# Carte_Alim_2020_TOP.net
KiCad netlist of a schematic drawn in Altium Designer
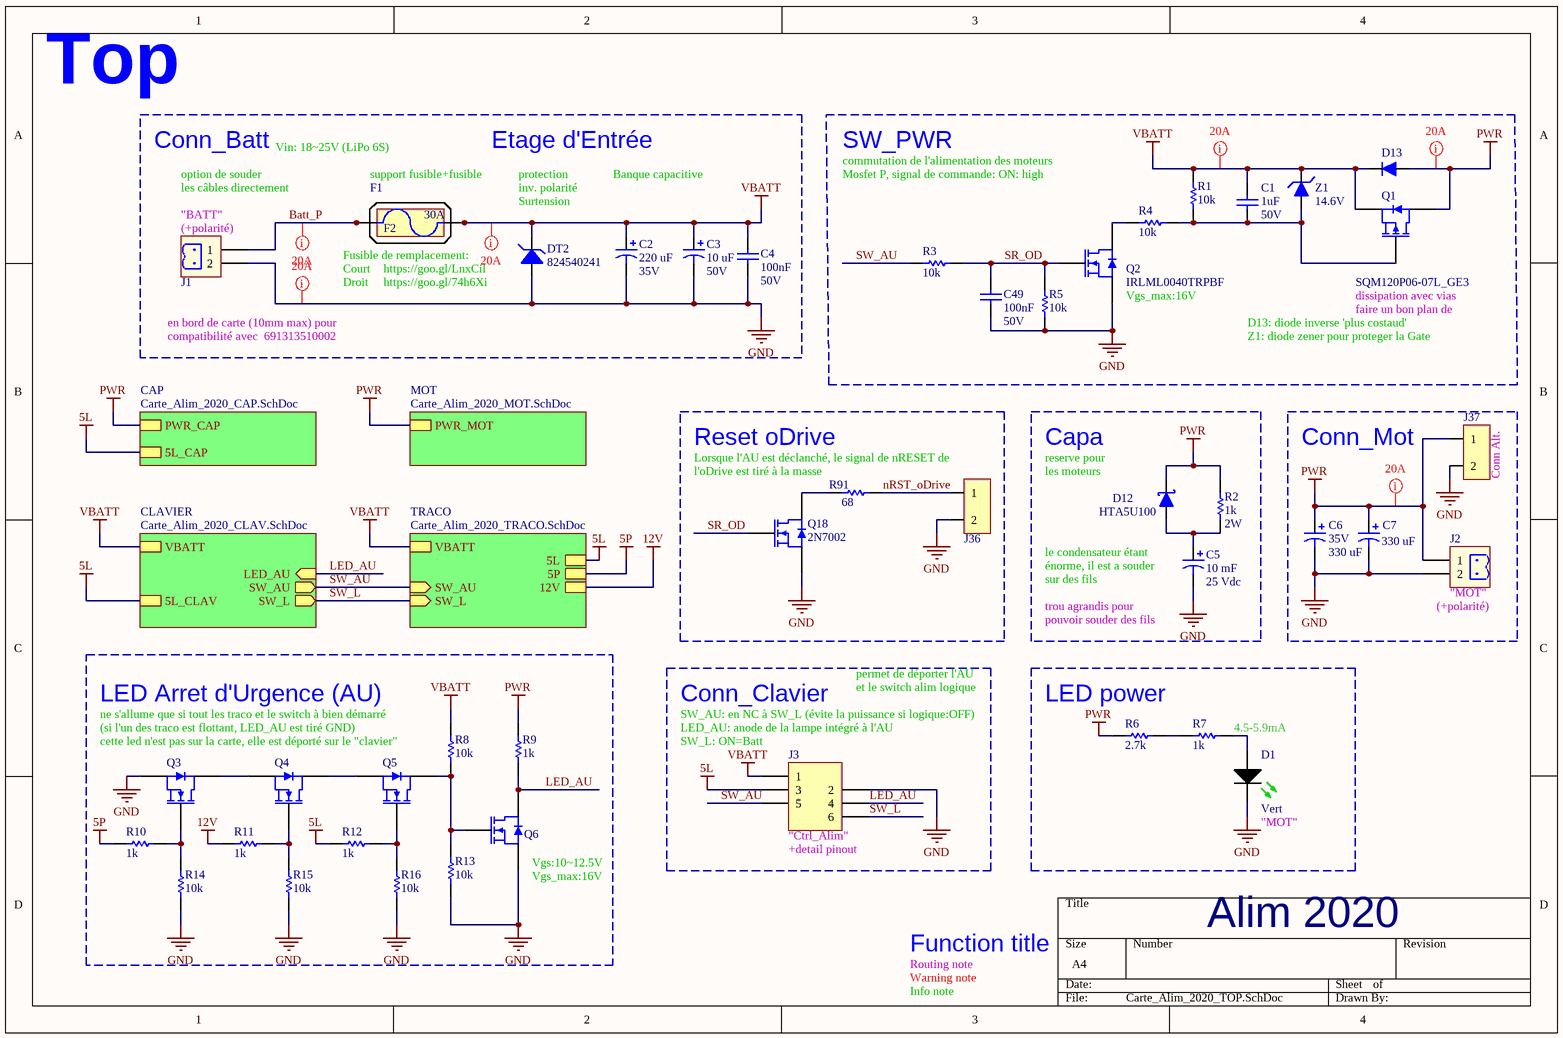
[diagram p0: Carte_Alim_2020_TOP.SchDoc]

(export (version "E")
  (design (tool "Eeschema 10.0.6"))
  (components
    (comp (ref "C1")
      (value "1uF")
      (footprint "WCAP-CSGP_0805, 2x1.25x1.25")
      (description "CAP CER 1uF 50V X7R 0805")
      (fields
        (field (name "MANUFACTURER") "Wurth Elektronik")
        (field (name "MANUFACTURER PART NUMBER") "885012207103")
        (field (name "RATEDVOLTAGE") "50V")
      )
      (libsource (lib "Condensateur") (part "WCAP-CSGP, 885012207103"))
    )
    (comp (ref "C2")
      (value "220 uF")
      (footprint "WCAP-ATG8_8x11.5x3.5x0.5")
      (description "CAP Alu 220 UF 20% 35 V")
      (fields
        (field (name "MANUFACTURER") "Wurth Elektronik")
        (field (name "MANUFACTURER PART NUMBER") "860010574011")
        (field (name "RATEDVOLTAGE") "35V")
      )
      (libsource (lib "Condensateur") (part "WCAP-ATG8, 860010574011"))
    )
    (comp (ref "C3")
      (value "10 uF")
      (footprint "WCAP-ATG8_5x11x2x0.5")
      (description "CAP Alu 10 UF 20% 50 V")
      (fields
        (field (name "RATEDVOLTAGE") "50V")
        (field (name "MANUFACTURER") "Wurth Elektronik")
        (field (name "MANUFACTURER PART NUMBER") "860010672009")
      )
      (libsource (lib "Condensateur") (part "WCAP-ATG8, 860010672009"))
    )
    (comp (ref "C4")
      (value "100nF")
      (footprint "WCAP-CSGP_0603, 1.6x0.8x0.8")
      (description "CAP CER 100nF 50V X7R 0603")
      (fields
        (field (name "RATEDVOLTAGE") "50V")
        (field (name "MANUFACTURER") "Wurth Elektronik")
        (field (name "MANUFACTURER PART NUMBER") "885012206095")
      )
      (libsource (lib "Condensateur") (part "WCAP-CSGP, 885012206095"))
    )
    (comp (ref "C5")
      (value "10 mF")
      (footprint "WCAP-ATG8_22x41x10x0.8")
      (description "CAP Alu 10'000 UF 25 V")
      (fields
        (field (name "MANUFACTURER PART NUMBER") "860010483029")
        (field (name "MANUFACTURER") "Wurth Elektronik")
        (field (name "RATED VOLTAGE") "25 Vdc")
      )
      (libsource (lib "Condensateur") (part "WCAP-ATG8, 860010483029"))
    )
    (comp (ref "C6")
      (value "330 uF")
      (footprint "WCAP-ATG8_10x12.5x5x0.6")
      (description "CAP Alu 330 UF 20% 35 V")
      (fields
        (field (name "MANUFACTURER") "Wurth Elektronik")
        (field (name "MANUFACTURER PART NUMBER") "860010575012")
        (field (name "RATEDVOLTAGE") "35V")
      )
      (libsource (lib "Condensateur") (part "WCAP-ATG8, 860010575012"))
    )
    (comp (ref "C7")
      (value "330 uF")
      (footprint "WCAP-ATG8_10x12.5x5x0.6")
      (description "CAP Alu 330 UF 20% 35 V")
      (fields
        (field (name "MANUFACTURER") "Wurth Elektronik")
        (field (name "MANUFACTURER PART NUMBER") "860010575012")
      )
      (libsource (lib "Condensateur") (part "WCAP-ATG8, 860010575012"))
    )
    (comp (ref "C49")
      (value "100nF")
      (footprint "WCAP-CSGP_0603, 1.6x0.8x0.8")
      (description "CAP CER 100nF 50V X7R 0603")
      (fields
        (field (name "RATEDVOLTAGE") "50V")
        (field (name "MANUFACTURER") "Wurth Elektronik")
        (field (name "MANUFACTURER PART NUMBER") "885012206095")
      )
      (libsource (lib "Condensateur") (part "WCAP-CSGP, 885012206095"))
    )
    (comp (ref "D1")
      (value "Vert")
      (footprint "SMCW_0603")
      (description "SMD mono-color Chip LED, WL-SMCW, Green")
      (fields
        (field (name "MANUFACTURER PART NUMBER") "150060GS75000")
        (field (name "CREATED BY") "Christin Otto")
      )
      (libsource (lib "Optoélectronique") (part "WL-SMCW 0603  150060GS75000"))
    )
    (comp (ref "D12")
      (value "HTA5U100")
      (footprint "SMA Diode (DO-214AC)")
      (description "DIODE SCHOTTKY 100V 5A SMA (DO-214AC)")
      (fields (field (name "MANUFACTURER") "MULTICOMP"))
      (libsource (lib "Diode") (part "HTA5U100"))
    )
    (comp (ref "D13")
      (value "RS3J R6")
      (footprint "DO-214AB_Unidirectional")
      (description "DIODE GEN PURP 600V 3A SMC")
      (fields (field (name "MANUFACTURER") "TAIWAN SEMICONDUCTOR"))
      (libsource (lib "Diode") (part "RS3J_R6"))
    )
    (comp (ref "DT2")
      (value "824540241")
      (footprint "DO-214AB_Unidirectional")
      (description "WE-TVSP Power TVS Diode, Unidirectional, 1500 W, 24 VDC")
      (fields (field (name "MANUFACTURER") "Wurth Electronics Inc."))
      (libsource (lib "Diode") (part "824540241"))
    )
    (comp (ref "F1")
      (value "3557-2")
      (footprint "3557-2")
      (description "FUSE Holder 500V 30A PCB")
      (fields (field (name "MANUFACTURER") "Keystone Electronics"))
      (libsource (lib "Fuse") (part "3557-2"))
    )
    (comp (ref "F2")
      (value "0891030.NXS")
      (description "FUSE AUTO 30A 58VDC BLADE MINI")
      (fields (field (name "MANUFACTURER") "Littelfuse Inc.") (field (name "COURANT NOMINAL") "30A"))
      (libsource (lib "Fuse") (part "0891030.NXS"))
    )
    (comp (ref "J1")
      (value "691311500102")
      (footprint "691311500102")
      (description "WR-TBL 2p Series 311 - 5.08 mm Closed Vertical PCB Header")
      (fields (field (name "MANUFACTURER") "Wurth Electronics Inc."))
      (libsource (lib "") (part "691311500102_1"))
    )
    (comp (ref "J2")
      (value "691311500102")
      (footprint "691311500102")
      (description "WR-TBL 2p Series 311 - 5.08 mm Closed Vertical PCB Header")
      (fields (field (name "MANUFACTURER") "Wurth Electronics Inc."))
      (libsource (lib "Connecteurs") (part "691311500102"))
    )
    (comp (ref "J3")
      (value "690367280676")
      (footprint "690367280676")
      (description "WR-MM 6p Female SMT Connector with Polarization")
      (fields (field (name "MANUFACTURER") "Wurth Electronics Inc."))
      (libsource (lib "Connecteurs") (part "690367280676"))
    )
    (comp (ref "J36")
      (value "22-03-2021")
      (footprint "22-03-2021")
      (libsource (lib "Connecteurs") (part "22-03-2021"))
    )
    (comp (ref "J37")
      (value "22-03-2021")
      (footprint "22-03-2021")
      (libsource (lib "Connecteurs") (part "22-03-2021"))
    )
    (comp (ref "Q1")
      (value "SQM120P06-07L_GE3")
      (footprint "TO-263")
      (description "MOSFET P 60V 120A D2PAK")
      (fields (field (name "MANUFACTURER") "VISHAY"))
      (libsource (lib "Transistors") (part "SQM120P06-07L_GE3"))
    )
    (comp (ref "Q2")
      (value "IRLML0040TRPBF")
      (footprint "SOT-23")
      (description "MOSFET N 40V 3.6A SOT23")
      (fields (field (name "MANUFACTURER") "INTERNATIONAL RECTIFIER"))
      (libsource (lib "Transistors") (part "IRLML0040"))
    )
    (comp (ref "Q3")
      (value "IRLML0040TRPBF")
      (footprint "SOT-23")
      (description "MOSFET N 40V 3.6A SOT23")
      (fields (field (name "MANUFACTURER") "INTERNATIONAL RECTIFIER"))
      (libsource (lib "Transistors") (part "IRLML0040"))
    )
    (comp (ref "Q4")
      (value "IRLML0040TRPBF")
      (footprint "SOT-23")
      (description "MOSFET N 40V 3.6A SOT23")
      (fields (field (name "MANUFACTURER") "INTERNATIONAL RECTIFIER"))
      (libsource (lib "Transistors") (part "IRLML0040"))
    )
    (comp (ref "Q5")
      (value "IRLML0040TRPBF")
      (footprint "SOT-23")
      (description "MOSFET N 40V 3.6A SOT23")
      (fields (field (name "MANUFACTURER") "INTERNATIONAL RECTIFIER"))
      (libsource (lib "Transistors") (part "IRLML0040"))
    )
    (comp (ref "Q6")
      (value "IRLML0040TRPBF")
      (footprint "SOT-23")
      (description "MOSFET N 40V 3.6A SOT23")
      (fields (field (name "MANUFACTURER") "INTERNATIONAL RECTIFIER"))
      (libsource (lib "Transistors") (part "IRLML0040"))
    )
    (comp (ref "Q18")
      (value "2N7002")
      (footprint "SOT-23")
      (description "MOSFET N 60V 115MA SOT-23")
      (fields (field (name "MANUFACTURER") "Changjiang Electronics Tech (CJ)"))
      (libsource (lib "Transistors") (part "2N7002"))
    )
    (comp (ref "R1")
      (value "10k")
      (footprint "RESC1608X06N")
      (description "RES SMD 10K OHM 1% 1/10W 0603")
      (fields
        (field (name "MANUFACTURER") "Yageo")
        (field (name "MANUFACTURER PART NUMBER") "RC0603FR-0710KL")
      )
      (libsource (lib "Resistance") (part "RC0603FR-0710KL"))
    )
    (comp (ref "R2")
      (value "1k")
      (footprint "RESADV480W80L1200D390")
      (description "resistance traversante verticale générique")
      (fields
        (field (name "MANUFACTURER") "MULTICOMP")
        (field (name "MANUFACTURER PART NUMBER") "MCKNP02WJ0102A19")
        (field (name "POWER") "2W")
      )
      (libsource (lib "Resistance") (part "Generic_TH_Vert_Res"))
    )
    (comp (ref "R3")
      (value "10k")
      (footprint "RESC1608X06N")
      (description "RES SMD 10K OHM 1% 1/10W 0603")
      (fields
        (field (name "MANUFACTURER") "Yageo")
        (field (name "MANUFACTURER PART NUMBER") "RC0603FR-0710KL")
      )
      (libsource (lib "Resistance") (part "RC0603FR-0710KL"))
    )
    (comp (ref "R4")
      (value "10k")
      (footprint "RESC1608X06N")
      (description "RES SMD 10K OHM 1% 1/10W 0603")
      (fields
        (field (name "MANUFACTURER") "Yageo")
        (field (name "MANUFACTURER PART NUMBER") "RC0603FR-0710KL")
      )
      (libsource (lib "Resistance") (part "RC0603FR-0710KL"))
    )
    (comp (ref "R5")
      (value "10k")
      (footprint "RESC1608X06N")
      (description "RES SMD 10K OHM 1% 1/10W 0603")
      (fields
        (field (name "MANUFACTURER") "Yageo")
        (field (name "MANUFACTURER PART NUMBER") "RC0603FR-0710KL")
      )
      (libsource (lib "Resistance") (part "RC0603FR-0710KL"))
    )
    (comp (ref "R6")
      (value "2.7k")
      (footprint "RESC2012X06M")
      (description "RES SMD 2K7 OHM 1% 1/8W 0805")
      (fields
        (field (name "MANUFACTURER") "Yageo")
        (field (name "MANUFACTURER PART NUMBER") "RC0805FR-072K7L")
      )
      (libsource (lib "Resistance") (part "RC0805FR-072K7L"))
    )
    (comp (ref "R7")
      (value "1k")
      (footprint "RESC1608X06N")
      (description "RES SMD 1K OHM 1% 1/10W 0603")
      (fields
        (field (name "MANUFACTURER") "Yageo")
        (field (name "MANUFACTURER PART NUMBER") "RC0603FR-071KL")
      )
      (libsource (lib "Resistance") (part "RC0603FR-071KL"))
    )
    (comp (ref "R8")
      (value "10k")
      (footprint "RESC1608X06N")
      (description "RES SMD 10K OHM 1% 1/10W 0603")
      (fields
        (field (name "MANUFACTURER") "Yageo")
        (field (name "MANUFACTURER PART NUMBER") "RC0603FR-0710KL")
      )
      (libsource (lib "Resistance") (part "RC0603FR-0710KL"))
    )
    (comp (ref "R9")
      (value "1k")
      (footprint "RESC1608X06N")
      (description "RES SMD 1K OHM 1% 1/10W 0603")
      (fields
        (field (name "MANUFACTURER") "Yageo")
        (field (name "MANUFACTURER PART NUMBER") "RC0603FR-071KL")
      )
      (libsource (lib "Resistance") (part "RC0603FR-071KL"))
    )
    (comp (ref "R10")
      (value "1k")
      (footprint "RESC1608X06N")
      (description "RES SMD 1K OHM 1% 1/10W 0603")
      (fields
        (field (name "MANUFACTURER") "Yageo")
        (field (name "MANUFACTURER PART NUMBER") "RC0603FR-071KL")
      )
      (libsource (lib "Resistance") (part "RC0603FR-071KL"))
    )
    (comp (ref "R11")
      (value "1k")
      (footprint "RESC1608X06N")
      (description "RES SMD 1K OHM 1% 1/10W 0603")
      (fields
        (field (name "MANUFACTURER") "Yageo")
        (field (name "MANUFACTURER PART NUMBER") "RC0603FR-071KL")
      )
      (libsource (lib "Resistance") (part "RC0603FR-071KL"))
    )
    (comp (ref "R12")
      (value "1k")
      (footprint "RESC1608X06N")
      (description "RES SMD 1K OHM 1% 1/10W 0603")
      (fields
        (field (name "MANUFACTURER") "Yageo")
        (field (name "MANUFACTURER PART NUMBER") "RC0603FR-071KL")
      )
      (libsource (lib "Resistance") (part "RC0603FR-071KL"))
    )
    (comp (ref "R13")
      (value "10k")
      (footprint "RESC1608X06N")
      (description "RES SMD 10K OHM 1% 1/10W 0603")
      (fields
        (field (name "MANUFACTURER") "Yageo")
        (field (name "MANUFACTURER PART NUMBER") "RC0603FR-0710KL")
      )
      (libsource (lib "Resistance") (part "RC0603FR-0710KL"))
    )
    (comp (ref "R14")
      (value "10k")
      (footprint "RESC1608X06N")
      (description "RES SMD 10K OHM 1% 1/10W 0603")
      (fields
        (field (name "MANUFACTURER") "Yageo")
        (field (name "MANUFACTURER PART NUMBER") "RC0603FR-0710KL")
      )
      (libsource (lib "Resistance") (part "RC0603FR-0710KL"))
    )
    (comp (ref "R15")
      (value "10k")
      (footprint "RESC1608X06N")
      (description "RES SMD 10K OHM 1% 1/10W 0603")
      (fields
        (field (name "MANUFACTURER") "Yageo")
        (field (name "MANUFACTURER PART NUMBER") "RC0603FR-0710KL")
      )
      (libsource (lib "Resistance") (part "RC0603FR-0710KL"))
    )
    (comp (ref "R16")
      (value "10k")
      (footprint "RESC1608X06N")
      (description "RES SMD 10K OHM 1% 1/10W 0603")
      (fields
        (field (name "MANUFACTURER") "Yageo")
        (field (name "MANUFACTURER PART NUMBER") "RC0603FR-0710KL")
      )
      (libsource (lib "Resistance") (part "RC0603FR-0710KL"))
    )
    (comp (ref "R91")
      (value "68")
      (footprint "RESC1608X06N")
      (description "RES SMD 68 OHM 1% 1/10W 0603")
      (fields
        (field (name "MANUFACTURER") "Yageo")
        (field (name "MANUFACTURER PART NUMBER") "RC0603FR-0768RL")
      )
      (libsource (lib "Resistance") (part "RC0603FR-0768RL"))
    )
    (comp (ref "Z1")
      (value "14.6V")
      (footprint "SOD-323")
      (description "DIODE ZENER 14.6V 300mW SOD323")
      (fields
        (field (name "MANUFACTURER") "ON Semiconductor")
        (field (name "MANUFACTURER PART NUMBER") "MM3Z15VST1G")
      )
      (libsource (lib "Diode") (part "MM3Z15VST1G"))
    )
  )
  (nets
    (net (code "1") (name "/Batt_P") (class "Default")
      (node (ref "F1") (pin "1") (pinfunction "1_1") (pintype "passive"))
      (node (ref "F1") (pin "3") (pinfunction "3_3") (pintype "passive"))
      (node (ref "J1") (pin "1") (pinfunction "1_1") (pintype "passive"))
    )
    (net (code "2") (name "/LED_AU") (class "Default")
      (node (ref "J3") (pin "4") (pinfunction "4_4") (pintype "passive"))
      (node (ref "Q6") (pin "3") (pinfunction "D_3") (pintype "passive"))
      (node (ref "R9") (pin "1") (pinfunction "1_1") (pintype "passive"))
    )
    (net (code "3") (name "/SR_OD") (class "Default")
      (node (ref "C49") (pin "2") (pinfunction "2_2") (pintype "passive"))
      (node (ref "Q18") (pin "1") (pinfunction "G_1") (pintype "passive"))
      (node (ref "Q2") (pin "1") (pinfunction "G_1") (pintype "passive"))
      (node (ref "R3") (pin "2") (pinfunction "2_2") (pintype "passive"))
      (node (ref "R5") (pin "1") (pinfunction "1_1") (pintype "passive"))
    )
    (net (code "4") (name "/SW_AU") (class "Default")
      (node (ref "J3") (pin "5") (pinfunction "5_5") (pintype "passive"))
      (node (ref "R3") (pin "1") (pinfunction "1_1") (pintype "passive"))
    )
    (net (code "5") (name "/SW_L") (class "Default")
      (node (ref "J3") (pin "6") (pinfunction "6_6") (pintype "passive"))
    )
    (net (code "6") (name "/nRST_oDrive") (class "Default")
      (node (ref "J36") (pin "1") (pinfunction "1_1") (pintype "passive"))
      (node (ref "R91") (pin "2") (pinfunction "2_2") (pintype "passive"))
    )
    (net (code "7") (name "5L") (class "Default")
      (node (ref "J3") (pin "3") (pinfunction "3_3") (pintype "passive"))
      (node (ref "R12") (pin "2") (pinfunction "2_2") (pintype "passive"))
    )
    (net (code "8") (name "5P") (class "Default")
      (node (ref "R10") (pin "2") (pinfunction "2_2") (pintype "passive"))
    )
    (net (code "9") (name "12V") (class "Default")
      (node (ref "R11") (pin "2") (pinfunction "2_2") (pintype "passive"))
    )
    (net (code "10") (name "GND") (class "Default")
      (node (ref "C2") (pin "2") (pinfunction "2_2") (pintype "passive"))
      (node (ref "C3") (pin "2") (pinfunction "2_2") (pintype "passive"))
      (node (ref "C4") (pin "1") (pinfunction "1_1") (pintype "passive"))
      (node (ref "C49") (pin "1") (pinfunction "1_1") (pintype "passive"))
      (node (ref "C5") (pin "2") (pinfunction "2_2") (pintype "passive"))
      (node (ref "C6") (pin "2") (pinfunction "2_2") (pintype "passive"))
      (node (ref "C7") (pin "2") (pinfunction "2_2") (pintype "passive"))
      (node (ref "D1") (pin "1") (pinfunction "C_1") (pintype "passive"))
      (node (ref "DT2") (pin "1") (pintype "passive"))
      (node (ref "J1") (pin "2") (pinfunction "2_2") (pintype "passive"))
      (node (ref "J2") (pin "2") (pinfunction "2_2") (pintype "passive"))
      (node (ref "J3") (pin "2") (pinfunction "2_2") (pintype "passive"))
      (node (ref "J36") (pin "2") (pinfunction "2_2") (pintype "passive"))
      (node (ref "J37") (pin "2") (pinfunction "2_2") (pintype "passive"))
      (node (ref "Q18") (pin "2") (pinfunction "S_2") (pintype "passive"))
      (node (ref "Q2") (pin "2") (pinfunction "S_2") (pintype "passive"))
      (node (ref "Q3") (pin "2") (pinfunction "S_2") (pintype "passive"))
      (node (ref "Q6") (pin "2") (pinfunction "S_2") (pintype "passive"))
      (node (ref "R13") (pin "1") (pinfunction "1_1") (pintype "passive"))
      (node (ref "R14") (pin "1") (pinfunction "1_1") (pintype "passive"))
      (node (ref "R15") (pin "1") (pinfunction "1_1") (pintype "passive"))
      (node (ref "R16") (pin "1") (pinfunction "1_1") (pintype "passive"))
      (node (ref "R5") (pin "2") (pinfunction "2_2") (pintype "passive"))
    )
    (net (code "11") (name "Net-(C5-Pad1)") (class "Default")
      (node (ref "C5") (pin "1") (pinfunction "1_1") (pintype "passive"))
      (node (ref "D12") (pin "1") (pintype "passive"))
      (node (ref "R2") (pin "2") (pinfunction "2_2") (pintype "passive"))
    )
    (net (code "12") (name "Net-(D1-A)") (class "Default")
      (node (ref "D1") (pin "2") (pinfunction "A_2") (pintype "passive"))
      (node (ref "R7") (pin "1") (pinfunction "1_1") (pintype "passive"))
    )
    (net (code "13") (name "Net-(Q1-G)") (class "Default")
      (node (ref "C1") (pin "1") (pinfunction "1_1") (pintype "passive"))
      (node (ref "Q1") (pin "1") (pinfunction "G_1") (pintype "passive"))
      (node (ref "R1") (pin "1") (pinfunction "1_1") (pintype "passive"))
      (node (ref "R4") (pin "1") (pinfunction "1_1") (pintype "passive"))
      (node (ref "Z1") (pin "1") (pintype "passive"))
    )
    (net (code "14") (name "Net-(Q2-D)") (class "Default")
      (node (ref "Q2") (pin "3") (pinfunction "D_3") (pintype "passive"))
      (node (ref "R4") (pin "2") (pinfunction "2_2") (pintype "passive"))
    )
    (net (code "15") (name "Net-(Q3-D)") (class "Default")
      (node (ref "Q3") (pin "3") (pinfunction "D_3") (pintype "passive"))
      (node (ref "Q4") (pin "2") (pinfunction "S_2") (pintype "passive"))
    )
    (net (code "16") (name "Net-(Q3-G)") (class "Default")
      (node (ref "Q3") (pin "1") (pinfunction "G_1") (pintype "passive"))
      (node (ref "R10") (pin "1") (pinfunction "1_1") (pintype "passive"))
      (node (ref "R14") (pin "2") (pinfunction "2_2") (pintype "passive"))
    )
    (net (code "17") (name "Net-(Q4-D)") (class "Default")
      (node (ref "Q4") (pin "3") (pinfunction "D_3") (pintype "passive"))
      (node (ref "Q5") (pin "2") (pinfunction "S_2") (pintype "passive"))
    )
    (net (code "18") (name "Net-(Q4-G)") (class "Default")
      (node (ref "Q4") (pin "1") (pinfunction "G_1") (pintype "passive"))
      (node (ref "R11") (pin "1") (pinfunction "1_1") (pintype "passive"))
      (node (ref "R15") (pin "2") (pinfunction "2_2") (pintype "passive"))
    )
    (net (code "19") (name "Net-(Q5-D)") (class "Default")
      (node (ref "Q5") (pin "3") (pinfunction "D_3") (pintype "passive"))
      (node (ref "Q6") (pin "1") (pinfunction "G_1") (pintype "passive"))
      (node (ref "R13") (pin "2") (pinfunction "2_2") (pintype "passive"))
      (node (ref "R8") (pin "1") (pinfunction "1_1") (pintype "passive"))
    )
    (net (code "20") (name "Net-(Q5-G)") (class "Default")
      (node (ref "Q5") (pin "1") (pinfunction "G_1") (pintype "passive"))
      (node (ref "R12") (pin "1") (pinfunction "1_1") (pintype "passive"))
      (node (ref "R16") (pin "2") (pinfunction "2_2") (pintype "passive"))
    )
    (net (code "21") (name "Net-(Q18-D)") (class "Default")
      (node (ref "Q18") (pin "3") (pinfunction "D_3") (pintype "passive"))
      (node (ref "R91") (pin "1") (pinfunction "1_1") (pintype "passive"))
    )
    (net (code "22") (name "Net-(R6-Pad2)") (class "Default")
      (node (ref "R6") (pin "2") (pinfunction "2_2") (pintype "passive"))
      (node (ref "R7") (pin "2") (pinfunction "2_2") (pintype "passive"))
    )
    (net (code "23") (name "PWR") (class "Default")
      (node (ref "C6") (pin "1") (pinfunction "1_1") (pintype "passive"))
      (node (ref "C7") (pin "1") (pinfunction "1_1") (pintype "passive"))
      (node (ref "D12") (pin "2") (pintype "passive"))
      (node (ref "D13") (pin "1") (pintype "passive"))
      (node (ref "J2") (pin "1") (pinfunction "1_1") (pintype "passive"))
      (node (ref "J37") (pin "1") (pinfunction "1_1") (pintype "passive"))
      (node (ref "Q1") (pin "4") (pinfunction "D_4") (pintype "passive"))
      (node (ref "R2") (pin "1") (pinfunction "1_1") (pintype "passive"))
      (node (ref "R6") (pin "1") (pinfunction "1_1") (pintype "passive"))
      (node (ref "R9") (pin "2") (pinfunction "2_2") (pintype "passive"))
    )
    (net (code "24") (name "VBATT") (class "Default")
      (node (ref "C1") (pin "2") (pinfunction "2_2") (pintype "passive"))
      (node (ref "C2") (pin "1") (pinfunction "1_1") (pintype "passive"))
      (node (ref "C3") (pin "1") (pinfunction "1_1") (pintype "passive"))
      (node (ref "C4") (pin "2") (pinfunction "2_2") (pintype "passive"))
      (node (ref "D13") (pin "2") (pintype "passive"))
      (node (ref "DT2") (pin "2") (pintype "passive"))
      (node (ref "F1") (pin "2") (pinfunction "2_2") (pintype "passive"))
      (node (ref "F1") (pin "4") (pinfunction "4_4") (pintype "passive"))
      (node (ref "J3") (pin "1") (pinfunction "1_1") (pintype "passive"))
      (node (ref "Q1") (pin "3") (pinfunction "S_3") (pintype "passive"))
      (node (ref "R1") (pin "2") (pinfunction "2_2") (pintype "passive"))
      (node (ref "R8") (pin "2") (pinfunction "2_2") (pintype "passive"))
      (node (ref "Z1") (pin "2") (pintype "passive"))
    )
  )
)
